# mixer_bolock.net
KiCad netlist of a schematic drawn in EAGLE
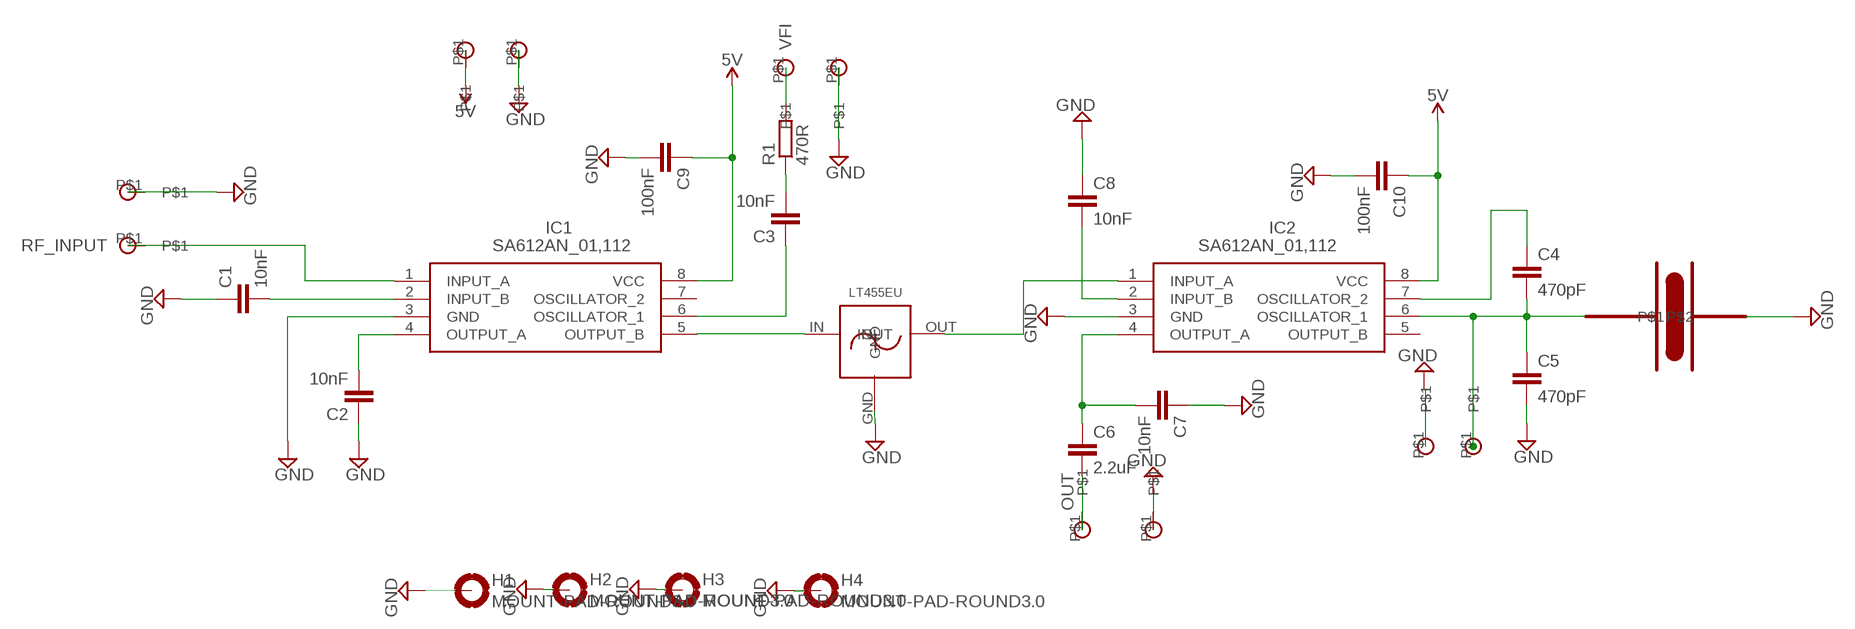
[diagram p0: schematic, sheet 1]

(export (version "E")
  (design (tool "Eeschema 10.0.6"))
  (components
    (comp (ref "+5")
      (value "SMD_PIN")
      (footprint "eagle-import:SMD_PIN")
      (libsource (lib "eagle-import") (part "SMD_PIN"))
    )
    (comp (ref "BFI")
      (value "SMD_PIN")
      (footprint "eagle-import:SMD_PIN")
      (libsource (lib "eagle-import") (part "SMD_PIN"))
    )
    (comp (ref "C1")
      (value "10nF")
      (footprint "eagle-import:C0805K")
      (libsource (lib "eagle-import") (part "C-EUC0805K"))
    )
    (comp (ref "C2")
      (value "10nF")
      (footprint "eagle-import:C0805K")
      (libsource (lib "eagle-import") (part "C-EUC0805K"))
    )
    (comp (ref "C3")
      (value "10nF")
      (footprint "eagle-import:C0805K")
      (libsource (lib "eagle-import") (part "C-EUC0805K"))
    )
    (comp (ref "C4")
      (value "470pF")
      (footprint "eagle-import:C0805K")
      (libsource (lib "eagle-import") (part "C-EUC0805K"))
    )
    (comp (ref "C5")
      (value "470pF")
      (footprint "eagle-import:C0805K")
      (libsource (lib "eagle-import") (part "C-EUC0805K"))
    )
    (comp (ref "C6")
      (value "2.2uF")
      (footprint "eagle-import:C050-050X075")
      (libsource (lib "eagle-import") (part "C-EU050-050X075"))
    )
    (comp (ref "C7")
      (value "10nF")
      (footprint "eagle-import:C0805K")
      (libsource (lib "eagle-import") (part "C-EUC0805K"))
    )
    (comp (ref "C8")
      (value "10nF")
      (footprint "eagle-import:C0805K")
      (libsource (lib "eagle-import") (part "C-EUC0805K"))
    )
    (comp (ref "C9")
      (value "100nF")
      (footprint "eagle-import:C0805K")
      (libsource (lib "eagle-import") (part "C-EUC0805K"))
    )
    (comp (ref "C10")
      (value "100nF")
      (footprint "eagle-import:C0805K")
      (libsource (lib "eagle-import") (part "C-EUC0805K"))
    )
    (comp (ref "H1")
      (value "MOUNT-PAD-ROUND3.0")
      (footprint "eagle-import:3,0-PAD")
      (libsource (lib "eagle-import") (part "MOUNT-PAD-ROUND3.0"))
    )
    (comp (ref "H2")
      (value "MOUNT-PAD-ROUND3.0")
      (footprint "eagle-import:3,0-PAD")
      (libsource (lib "eagle-import") (part "MOUNT-PAD-ROUND3.0"))
    )
    (comp (ref "H3")
      (value "MOUNT-PAD-ROUND3.0")
      (footprint "eagle-import:3,0-PAD")
      (libsource (lib "eagle-import") (part "MOUNT-PAD-ROUND3.0"))
    )
    (comp (ref "H4")
      (value "MOUNT-PAD-ROUND3.0")
      (footprint "eagle-import:3,0-PAD")
      (libsource (lib "eagle-import") (part "MOUNT-PAD-ROUND3.0"))
    )
    (comp (ref "IC1")
      (value "SA612AN_01,112")
      (footprint "eagle-import:DIP762W53P254L950H420Q8N")
      (fields
        (field (name "MANUFACTURER_PART_NUMBER") "SA612AN/01,112")
        (field (name "MOUSER_PART_NUMBER") "771-SA612AN/01")
      )
      (libsource (lib "eagle-import") (part "SA612AN_01,112"))
    )
    (comp (ref "IC2")
      (value "SA612AN_01,112")
      (footprint "eagle-import:DIP762W53P254L950H420Q8N")
      (fields
        (field (name "MANUFACTURER_PART_NUMBER") "SA612AN/01,112")
        (field (name "MOUSER_PART_NUMBER") "771-SA612AN/01")
      )
      (libsource (lib "eagle-import") (part "SA612AN_01,112"))
    )
    (comp (ref "IN")
      (value "SMD_PIN")
      (footprint "eagle-import:SMD_PIN")
      (libsource (lib "eagle-import") (part "SMD_PIN"))
    )
    (comp (ref "OUT")
      (value "SMD_PIN")
      (footprint "eagle-import:SMD_PIN")
      (libsource (lib "eagle-import") (part "SMD_PIN"))
    )
    (comp (ref "R1")
      (value "470R")
      (footprint "eagle-import:R0805")
      (libsource (lib "eagle-import") (part "R-EU_R0805"))
    )
    (comp (ref "U$1")
      (value "ZTBF455E")
      (footprint "eagle-import:ZTBF455E")
      (libsource (lib "eagle-import") (part "ZTBF455E"))
    )
    (comp (ref "U$2")
      (value "SMD_PIN")
      (footprint "eagle-import:SMD_PIN")
      (libsource (lib "eagle-import") (part "SMD_PIN"))
    )
    (comp (ref "U$4")
      (value "SMD_PIN")
      (footprint "eagle-import:SMD_PIN")
      (libsource (lib "eagle-import") (part "SMD_PIN"))
    )
    (comp (ref "U$5")
      (value "SMD_PIN")
      (footprint "eagle-import:SMD_PIN")
      (libsource (lib "eagle-import") (part "SMD_PIN"))
    )
    (comp (ref "U$6")
      (value "SMD_PIN")
      (footprint "eagle-import:SMD_PIN")
      (libsource (lib "eagle-import") (part "SMD_PIN"))
    )
    (comp (ref "U$7")
      (value "SMD_PIN")
      (footprint "eagle-import:SMD_PIN")
      (libsource (lib "eagle-import") (part "SMD_PIN"))
    )
    (comp (ref "U$9")
      (value "LT455EU")
      (footprint "eagle-import:LT455EU")
      (libsource (lib "eagle-import") (part "LT455EU"))
    )
    (comp (ref "VFI")
      (value "SMD_PIN")
      (footprint "eagle-import:SMD_PIN")
      (libsource (lib "eagle-import") (part "SMD_PIN"))
    )
  )
  (nets
    (net (code "1") (name "/OUT") (class "Default")
      (node (ref "C6") (pin "2") (pinfunction "2_2") (pintype "passive"))
      (node (ref "OUT") (pin "P$1") (pinfunction "P$1_P$1") (pintype "bidirectional"))
    )
    (net (code "2") (name "/RF_INPUT") (class "Default")
      (node (ref "IC1") (pin "1") (pinfunction "INPUT_A_1") (pintype "bidirectional"))
      (node (ref "IN") (pin "P$1") (pinfunction "P$1_P$1") (pintype "bidirectional"))
    )
    (net (code "3") (name "/VFI") (class "Default")
      (node (ref "R1") (pin "2") (pinfunction "2_2") (pintype "passive"))
      (node (ref "VFI") (pin "P$1") (pinfunction "P$1_P$1") (pintype "bidirectional"))
    )
    (net (code "4") (name "5V") (class "Default")
      (node (ref "+5") (pin "P$1") (pinfunction "P$1_P$1") (pintype "bidirectional"))
      (node (ref "C10") (pin "1") (pinfunction "1_1") (pintype "passive"))
      (node (ref "C9") (pin "1") (pinfunction "1_1") (pintype "passive"))
      (node (ref "IC1") (pin "8") (pinfunction "VCC_8") (pintype "bidirectional"))
      (node (ref "IC2") (pin "8") (pinfunction "VCC_8") (pintype "bidirectional"))
    )
    (net (code "5") (name "GND") (class "Default")
      (node (ref "C1") (pin "1") (pinfunction "1_1") (pintype "passive"))
      (node (ref "C10") (pin "2") (pinfunction "2_2") (pintype "passive"))
      (node (ref "C2") (pin "1") (pinfunction "1_1") (pintype "passive"))
      (node (ref "C5") (pin "2") (pinfunction "2_2") (pintype "passive"))
      (node (ref "C7") (pin "1") (pinfunction "1_1") (pintype "passive"))
      (node (ref "C8") (pin "1") (pinfunction "1_1") (pintype "passive"))
      (node (ref "C9") (pin "2") (pinfunction "2_2") (pintype "passive"))
      (node (ref "H1") (pin "B3,0") (pinfunction "MOUNT_B3,0") (pintype "passive"))
      (node (ref "H2") (pin "B3,0") (pinfunction "MOUNT_B3,0") (pintype "passive"))
      (node (ref "H3") (pin "B3,0") (pinfunction "MOUNT_B3,0") (pintype "passive"))
      (node (ref "H4") (pin "B3,0") (pinfunction "MOUNT_B3,0") (pintype "passive"))
      (node (ref "IC1") (pin "3") (pinfunction "GND_3") (pintype "bidirectional"))
      (node (ref "IC2") (pin "3") (pinfunction "GND_3") (pintype "bidirectional"))
      (node (ref "U$1") (pin "P$2") (pinfunction "P$2_P$2") (pintype "output"))
      (node (ref "U$2") (pin "P$1") (pinfunction "P$1_P$1") (pintype "bidirectional"))
      (node (ref "U$4") (pin "P$1") (pinfunction "P$1_P$1") (pintype "bidirectional"))
      (node (ref "U$5") (pin "P$1") (pinfunction "P$1_P$1") (pintype "bidirectional"))
      (node (ref "U$6") (pin "P$1") (pinfunction "P$1_P$1") (pintype "bidirectional"))
      (node (ref "U$7") (pin "P$1") (pinfunction "P$1_P$1") (pintype "bidirectional"))
      (node (ref "U$9") (pin "GND") (pinfunction "GND_GND") (pintype "power_in"))
    )
    (net (code "6") (name "Net-(C3-Pad2)") (class "Default")
      (node (ref "C3") (pin "2") (pinfunction "2_2") (pintype "passive"))
      (node (ref "R1") (pin "1") (pinfunction "1_1") (pintype "passive"))
    )
    (net (code "7") (name "Net-(IC1-INPUT_B)") (class "Default")
      (node (ref "C1") (pin "2") (pinfunction "2_2") (pintype "passive"))
      (node (ref "IC1") (pin "2") (pinfunction "INPUT_B_2") (pintype "bidirectional"))
    )
    (net (code "8") (name "Net-(IC1-OSCILLATOR_1)") (class "Default")
      (node (ref "C3") (pin "1") (pinfunction "1_1") (pintype "passive"))
      (node (ref "IC1") (pin "6") (pinfunction "OSCILLATOR_1_6") (pintype "bidirectional"))
    )
    (net (code "9") (name "Net-(IC1-OUTPUT_A)") (class "Default")
      (node (ref "C2") (pin "2") (pinfunction "2_2") (pintype "passive"))
      (node (ref "IC1") (pin "4") (pinfunction "OUTPUT_A_4") (pintype "bidirectional"))
    )
    (net (code "10") (name "Net-(IC1-OUTPUT_B)") (class "Default")
      (node (ref "IC1") (pin "5") (pinfunction "OUTPUT_B_5") (pintype "bidirectional"))
      (node (ref "U$9") (pin "IN") (pinfunction "IN_IN") (pintype "input"))
    )
    (net (code "11") (name "Net-(IC2-INPUT_A)") (class "Default")
      (node (ref "IC2") (pin "1") (pinfunction "INPUT_A_1") (pintype "bidirectional"))
      (node (ref "U$9") (pin "OUT") (pinfunction "OUT_OUT") (pintype "output"))
    )
    (net (code "12") (name "Net-(IC2-INPUT_B)") (class "Default")
      (node (ref "C8") (pin "2") (pinfunction "2_2") (pintype "passive"))
      (node (ref "IC2") (pin "2") (pinfunction "INPUT_B_2") (pintype "bidirectional"))
    )
    (net (code "13") (name "Net-(IC2-OSCILLATOR_1)") (class "Default")
      (node (ref "BFI") (pin "P$1") (pinfunction "P$1_P$1") (pintype "bidirectional"))
      (node (ref "C4") (pin "2") (pinfunction "2_2") (pintype "passive"))
      (node (ref "C5") (pin "1") (pinfunction "1_1") (pintype "passive"))
      (node (ref "IC2") (pin "6") (pinfunction "OSCILLATOR_1_6") (pintype "bidirectional"))
      (node (ref "U$1") (pin "P$1") (pinfunction "P$1_P$1") (pintype "input"))
    )
    (net (code "14") (name "Net-(IC2-OSCILLATOR_2)") (class "Default")
      (node (ref "C4") (pin "1") (pinfunction "1_1") (pintype "passive"))
      (node (ref "IC2") (pin "7") (pinfunction "OSCILLATOR_2_7") (pintype "bidirectional"))
    )
    (net (code "15") (name "Net-(IC2-OUTPUT_A)") (class "Default")
      (node (ref "C6") (pin "1") (pinfunction "1_1") (pintype "passive"))
      (node (ref "C7") (pin "2") (pinfunction "2_2") (pintype "passive"))
      (node (ref "IC2") (pin "4") (pinfunction "OUTPUT_A_4") (pintype "bidirectional"))
    )
    (net (code "16") (name "unconnected-(IC1-OSCILLATOR_2-Pad7)") (class "Default")
      (node (ref "IC1") (pin "7") (pinfunction "OSCILLATOR_2_7") (pintype "bidirectional"))
    )
    (net (code "17") (name "unconnected-(IC2-OUTPUT_B-Pad5)") (class "Default")
      (node (ref "IC2") (pin "5") (pinfunction "OUTPUT_B_5") (pintype "bidirectional"))
    )
  )
)
